# UIPCB.net
KiCad netlist of a schematic drawn in EAGLE
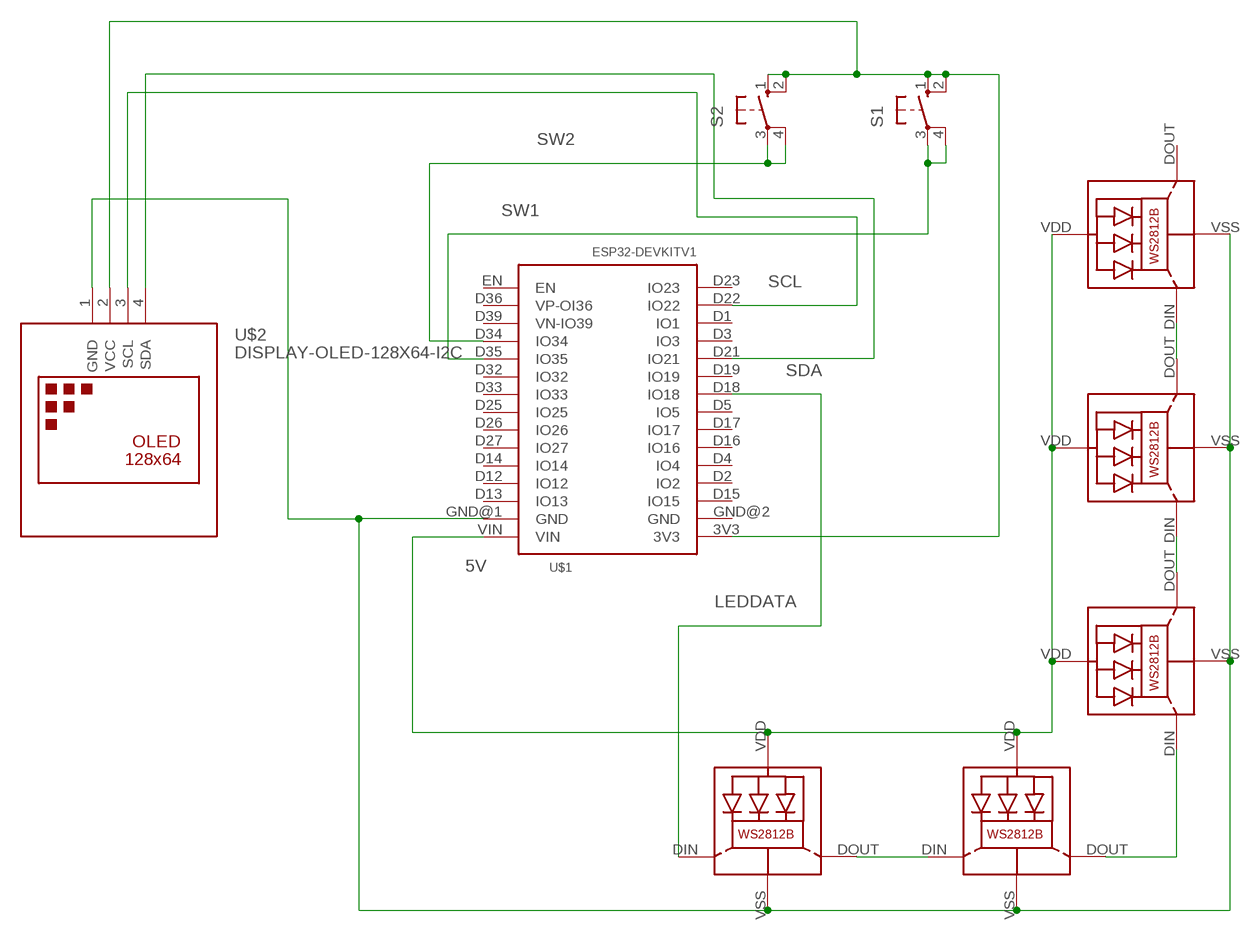
[diagram p0: schematic, sheet 1]

(export (version "E")
  (design (tool "Eeschema 10.0.6"))
  (components
    (comp (ref "LED0")
      (value "WS2812B")
      (footprint "eagle-import:WS2812B")
      (libsource (lib "eagle-import") (part "WS2812B"))
    )
    (comp (ref "LED1")
      (value "WS2812B")
      (footprint "eagle-import:WS2812B")
      (libsource (lib "eagle-import") (part "WS2812B"))
    )
    (comp (ref "LED2")
      (value "WS2812B")
      (footprint "eagle-import:WS2812B")
      (libsource (lib "eagle-import") (part "WS2812B"))
    )
    (comp (ref "LED3")
      (value "WS2812B")
      (footprint "eagle-import:WS2812B")
      (libsource (lib "eagle-import") (part "WS2812B"))
    )
    (comp (ref "LED4")
      (value "WS2812B")
      (footprint "eagle-import:WS2812B")
      (libsource (lib "eagle-import") (part "WS2812B"))
    )
    (comp (ref "S1")
      (value "10-XX")
      (footprint "eagle-import:B3F-10XX")
      (fields (field (name "MPN") "B3F-1000"))
      (libsource (lib "eagle-import") (part "10-XX"))
    )
    (comp (ref "S2")
      (value "10-XX")
      (footprint "eagle-import:B3F-10XX")
      (fields (field (name "MPN") "B3F-1000"))
      (libsource (lib "eagle-import") (part "10-XX"))
    )
    (comp (ref "U$1")
      (value "ESP32DEVKITV1")
      (footprint "eagle-import:ESP32-DEVKITV1")
      (libsource (lib "eagle-import") (part "ESP32DEVKITV1"))
    )
    (comp (ref "U$2")
      (value "DISPLAY-OLED-128X64-I2C")
      (footprint "eagle-import:DISPLAY-OLED-128X64-I2C")
      (libsource (lib "eagle-import") (part "DISPLAY-OLED-128X64-I2C"))
    )
  )
  (nets
    (net (code "1") (name "/5V") (class "Default")
      (node (ref "LED0") (pin "VDD") (pinfunction "VDD_VDD") (pintype "power_in"))
      (node (ref "LED1") (pin "VDD") (pinfunction "VDD_VDD") (pintype "power_in"))
      (node (ref "LED2") (pin "VDD") (pinfunction "VDD_VDD") (pintype "power_in"))
      (node (ref "LED3") (pin "VDD") (pinfunction "VDD_VDD") (pintype "power_in"))
      (node (ref "LED4") (pin "VDD") (pinfunction "VDD_VDD") (pintype "power_in"))
      (node (ref "U$1") (pin "VIN") (pinfunction "VIN_VIN") (pintype "bidirectional"))
    )
    (net (code "2") (name "/LEDDATA") (class "Default")
      (node (ref "LED0") (pin "DIN") (pinfunction "DI_DIN") (pintype "input"))
      (node (ref "U$1") (pin "D18") (pinfunction "IO18_D18") (pintype "bidirectional"))
    )
    (net (code "3") (name "/SCL") (class "Default")
      (node (ref "U$1") (pin "D22") (pinfunction "IO22_D22") (pintype "bidirectional"))
      (node (ref "U$2") (pin "3") (pinfunction "SCL_3") (pintype "bidirectional"))
    )
    (net (code "4") (name "/SDA") (class "Default")
      (node (ref "U$1") (pin "D21") (pinfunction "IO21_D21") (pintype "bidirectional"))
      (node (ref "U$2") (pin "4") (pinfunction "SDA_4") (pintype "bidirectional"))
    )
    (net (code "5") (name "/SW1") (class "Default")
      (node (ref "S1") (pin "3") (pinfunction "P_3") (pintype "passive"))
      (node (ref "S1") (pin "4") (pinfunction "P1_4") (pintype "passive"))
      (node (ref "U$1") (pin "D35") (pinfunction "IO35_D35") (pintype "bidirectional"))
    )
    (net (code "6") (name "/SW2") (class "Default")
      (node (ref "S2") (pin "3") (pinfunction "P_3") (pintype "passive"))
      (node (ref "S2") (pin "4") (pinfunction "P1_4") (pintype "passive"))
      (node (ref "U$1") (pin "D34") (pinfunction "IO34_D34") (pintype "bidirectional"))
    )
    (net (code "7") (name "Net-(LED0-DO)") (class "Default")
      (node (ref "LED0") (pin "DOUT") (pinfunction "DO_DOUT") (pintype "output"))
      (node (ref "LED1") (pin "DIN") (pinfunction "DI_DIN") (pintype "input"))
    )
    (net (code "8") (name "Net-(LED0-GND)") (class "Default")
      (node (ref "LED0") (pin "VSS") (pinfunction "GND_VSS") (pintype "power_in"))
      (node (ref "LED1") (pin "VSS") (pinfunction "GND_VSS") (pintype "power_in"))
      (node (ref "LED2") (pin "VSS") (pinfunction "GND_VSS") (pintype "power_in"))
      (node (ref "LED3") (pin "VSS") (pinfunction "GND_VSS") (pintype "power_in"))
      (node (ref "LED4") (pin "VSS") (pinfunction "GND_VSS") (pintype "power_in"))
      (node (ref "U$1") (pin "GND@1") (pinfunction "GND_GND@1") (pintype "bidirectional"))
      (node (ref "U$2") (pin "1") (pinfunction "GND_1") (pintype "power_in"))
    )
    (net (code "9") (name "Net-(LED1-DO)") (class "Default")
      (node (ref "LED1") (pin "DOUT") (pinfunction "DO_DOUT") (pintype "output"))
      (node (ref "LED2") (pin "DIN") (pinfunction "DI_DIN") (pintype "input"))
    )
    (net (code "10") (name "Net-(LED2-DO)") (class "Default")
      (node (ref "LED2") (pin "DOUT") (pinfunction "DO_DOUT") (pintype "output"))
      (node (ref "LED3") (pin "DIN") (pinfunction "DI_DIN") (pintype "input"))
    )
    (net (code "11") (name "Net-(LED3-DO)") (class "Default")
      (node (ref "LED3") (pin "DOUT") (pinfunction "DO_DOUT") (pintype "output"))
      (node (ref "LED4") (pin "DIN") (pinfunction "DI_DIN") (pintype "input"))
    )
    (net (code "12") (name "Net-(S1-S)") (class "Default")
      (node (ref "S1") (pin "1") (pinfunction "S_1") (pintype "passive"))
      (node (ref "S1") (pin "2") (pinfunction "S1_2") (pintype "passive"))
      (node (ref "S2") (pin "1") (pinfunction "S_1") (pintype "passive"))
      (node (ref "S2") (pin "2") (pinfunction "S1_2") (pintype "passive"))
      (node (ref "U$1") (pin "3V3") (pinfunction "3V3_3V3") (pintype "bidirectional"))
      (node (ref "U$2") (pin "2") (pinfunction "VCC_2") (pintype "power_in"))
    )
    (net (code "13") (name "unconnected-(LED4-DO-PadDOUT)") (class "Default")
      (node (ref "LED4") (pin "DOUT") (pinfunction "DO_DOUT") (pintype "output"))
    )
    (net (code "14") (name "unconnected-(U$1-GND-PadGND@2)") (class "Default")
      (node (ref "U$1") (pin "GND@2") (pinfunction "GND_GND@2") (pintype "bidirectional"))
    )
    (net (code "15") (name "unconnected-(U$1-IO1-PadD1)") (class "Default")
      (node (ref "U$1") (pin "D1") (pinfunction "IO1_D1") (pintype "bidirectional"))
    )
    (net (code "16") (name "unconnected-(U$1-IO2-PadD2)") (class "Default")
      (node (ref "U$1") (pin "D2") (pinfunction "IO2_D2") (pintype "bidirectional"))
    )
    (net (code "17") (name "unconnected-(U$1-IO3-PadD3)") (class "Default")
      (node (ref "U$1") (pin "D3") (pinfunction "IO3_D3") (pintype "bidirectional"))
    )
    (net (code "18") (name "unconnected-(U$1-IO4-PadD4)") (class "Default")
      (node (ref "U$1") (pin "D4") (pinfunction "IO4_D4") (pintype "bidirectional"))
    )
    (net (code "19") (name "unconnected-(U$1-IO5-PadD5)") (class "Default")
      (node (ref "U$1") (pin "D5") (pinfunction "IO5_D5") (pintype "bidirectional"))
    )
    (net (code "20") (name "unconnected-(U$1-IO12-PadD12)") (class "Default")
      (node (ref "U$1") (pin "D12") (pinfunction "IO12_D12") (pintype "bidirectional"))
    )
    (net (code "21") (name "unconnected-(U$1-IO13-PadD13)") (class "Default")
      (node (ref "U$1") (pin "D13") (pinfunction "IO13_D13") (pintype "bidirectional"))
    )
    (net (code "22") (name "unconnected-(U$1-IO14-PadD14)") (class "Default")
      (node (ref "U$1") (pin "D14") (pinfunction "IO14_D14") (pintype "bidirectional"))
    )
    (net (code "23") (name "unconnected-(U$1-IO15-PadD15)") (class "Default")
      (node (ref "U$1") (pin "D15") (pinfunction "IO15_D15") (pintype "bidirectional"))
    )
    (net (code "24") (name "unconnected-(U$1-IO16-PadD16)") (class "Default")
      (node (ref "U$1") (pin "D16") (pinfunction "IO16_D16") (pintype "bidirectional"))
    )
    (net (code "25") (name "unconnected-(U$1-IO17-PadD17)") (class "Default")
      (node (ref "U$1") (pin "D17") (pinfunction "IO17_D17") (pintype "bidirectional"))
    )
    (net (code "26") (name "unconnected-(U$1-IO19-PadD19)") (class "Default")
      (node (ref "U$1") (pin "D19") (pinfunction "IO19_D19") (pintype "bidirectional"))
    )
    (net (code "27") (name "unconnected-(U$1-IO23-PadD23)") (class "Default")
      (node (ref "U$1") (pin "D23") (pinfunction "IO23_D23") (pintype "bidirectional"))
    )
    (net (code "28") (name "unconnected-(U$1-IO25-PadD25)") (class "Default")
      (node (ref "U$1") (pin "D25") (pinfunction "IO25_D25") (pintype "bidirectional"))
    )
    (net (code "29") (name "unconnected-(U$1-IO26-PadD26)") (class "Default")
      (node (ref "U$1") (pin "D26") (pinfunction "IO26_D26") (pintype "bidirectional"))
    )
    (net (code "30") (name "unconnected-(U$1-IO27-PadD27)") (class "Default")
      (node (ref "U$1") (pin "D27") (pinfunction "IO27_D27") (pintype "bidirectional"))
    )
    (net (code "31") (name "unconnected-(U$1-IO32-PadD32)") (class "Default")
      (node (ref "U$1") (pin "D32") (pinfunction "IO32_D32") (pintype "bidirectional"))
    )
    (net (code "32") (name "unconnected-(U$1-IO33-PadD33)") (class "Default")
      (node (ref "U$1") (pin "D33") (pinfunction "IO33_D33") (pintype "bidirectional"))
    )
    (net (code "33") (name "unconnected-(U$1-PadEN)") (class "Default")
      (node (ref "U$1") (pin "EN") (pinfunction "EN_EN") (pintype "bidirectional"))
    )
    (net (code "34") (name "unconnected-(U$1-VN-IO39-PadD39)") (class "Default")
      (node (ref "U$1") (pin "D39") (pinfunction "VN-IO39_D39") (pintype "bidirectional"))
    )
    (net (code "35") (name "unconnected-(U$1-VP-OI36-PadD36)") (class "Default")
      (node (ref "U$1") (pin "D36") (pinfunction "VP-OI36_D36") (pintype "bidirectional"))
    )
  )
)
